# WCE_NanEyeC_board.net
KiCad netlist of a schematic drawn in Altium Designer
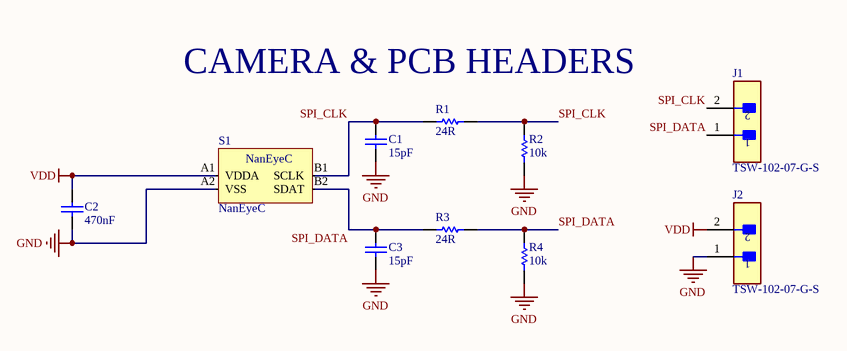
[diagram p0: WCE_NanEyeC_board.SchDoc]

(export (version "E")
  (design (tool "Eeschema 10.0.6"))
  (components
    (comp (ref "C1")
      (value "15pF")
      (footprint "CAPC1608X90X35NL15T15")
      (fields
        (field (name "MANUFACTURER") "AVX Interconnect / Elco")
        (field (name "PART NUMBER") "06035D104KAT2A")
      )
      (libsource (lib "Altium Content Vault") (part "CAP"))
    )
    (comp (ref "C2")
      (value "470nF")
      (footprint "CAPC1608X90X35NL15T15")
      (fields
        (field (name "MANUFACTURER") "AVX Interconnect / Elco")
        (field (name "PART NUMBER") "06035D104KAT2A")
      )
      (libsource (lib "Altium Content Vault") (part "CAP"))
    )
    (comp (ref "C3")
      (value "15pF")
      (footprint "CAPC1608X90X35NL15T15")
      (fields
        (field (name "MANUFACTURER") "AVX Interconnect / Elco")
        (field (name "PART NUMBER") "06035D104KAT2A")
      )
      (libsource (lib "Altium Content Vault") (part "CAP"))
    )
    (comp (ref "J1")
      (value "TSW-102-07-G-S")
      (footprint "FP-TSW-102-07-G-S-MFG")
      (description "CONN HEADER VERT 2POS 2.54MM")
      (fields
        (field (name "MANUFACTURER") "Samtec")
        (field (name "OCTOPART") "https://octopart.com/tsw-102-07-g-s-samtec-272197")
      )
      (libsource (lib "Altium Content Vault") (part "3bc925449376181038e59eaffc5286c"))
    )
    (comp (ref "J2")
      (value "TSW-102-07-G-S")
      (footprint "FP-TSW-102-07-G-S-MFG")
      (description "CONN HEADER VERT 2POS 2.54MM")
      (fields
        (field (name "MANUFACTURER") "Samtec")
        (field (name "OCTOPART") "https://octopart.com/tsw-102-07-g-s-samtec-272197")
      )
      (libsource (lib "Altium Content Vault") (part "3bc925449376181038e59eaffc5286c"))
    )
    (comp (ref "R1")
      (value "24R")
      (footprint "RESC1608X50X30ML20T20")
      (fields (field (name "PART NUMBER") "RR0816P-4640-D-65A") (field (name "MANUFACTURER") "Susumu"))
      (libsource (lib "Altium Content Vault") (part "RES"))
    )
    (comp (ref "R2")
      (value "10k")
      (footprint "RESC1608X50X30ML20T20")
      (fields (field (name "PART NUMBER") "RR0816P-4640-D-65A") (field (name "MANUFACTURER") "Susumu"))
      (libsource (lib "Altium Content Vault") (part "RES"))
    )
    (comp (ref "R3")
      (value "24R")
      (footprint "RESC1608X50X30ML20T20")
      (fields (field (name "PART NUMBER") "RR0816P-4640-D-65A") (field (name "MANUFACTURER") "Susumu"))
      (libsource (lib "Altium Content Vault") (part "RES"))
    )
    (comp (ref "R4")
      (value "10k")
      (footprint "RESC1608X50X30ML20T20")
      (fields (field (name "PART NUMBER") "RR0816P-4640-D-65A") (field (name "MANUFACTURER") "Susumu"))
      (libsource (lib "Altium Content Vault") (part "RES"))
    )
    (comp (ref "S1")
      (value "NanEyeC")
      (footprint "NanEyeC")
      (description "Camera module NanEyeC from AMS. The Part will be delivered by us")
      (libsource (lib "WCE_thesis") (part "NanEyeC"))
    )
  )
  (nets
    (net (code "1") (name "/SPI_CLK") (class "Default")
      (node (ref "C1") (pin "2") (pinfunction "2_2") (pintype "passive"))
      (node (ref "J1") (pin "2") (pinfunction "2_2") (pintype "passive"))
      (node (ref "R1") (pin "1") (pinfunction "1_1") (pintype "passive"))
      (node (ref "R1") (pin "2") (pinfunction "2_2") (pintype "passive"))
      (node (ref "R2") (pin "2") (pinfunction "2_2") (pintype "passive"))
      (node (ref "S1") (pin "B1") (pinfunction "SCLK_B1") (pintype "power_in"))
    )
    (net (code "2") (name "/SPI_DATA") (class "Default")
      (node (ref "C3") (pin "2") (pinfunction "2_2") (pintype "passive"))
      (node (ref "J1") (pin "1") (pinfunction "1_1") (pintype "passive"))
      (node (ref "R3") (pin "1") (pinfunction "1_1") (pintype "passive"))
      (node (ref "R3") (pin "2") (pinfunction "2_2") (pintype "passive"))
      (node (ref "R4") (pin "2") (pinfunction "2_2") (pintype "passive"))
      (node (ref "S1") (pin "B2") (pinfunction "SDAT_B2") (pintype "passive"))
    )
    (net (code "3") (name "GND") (class "Default")
      (node (ref "C1") (pin "1") (pinfunction "1_1") (pintype "passive"))
      (node (ref "C2") (pin "1") (pinfunction "1_1") (pintype "passive"))
      (node (ref "C3") (pin "1") (pinfunction "1_1") (pintype "passive"))
      (node (ref "J2") (pin "1") (pinfunction "1_1") (pintype "passive"))
      (node (ref "R2") (pin "1") (pinfunction "1_1") (pintype "passive"))
      (node (ref "R4") (pin "1") (pinfunction "1_1") (pintype "passive"))
      (node (ref "S1") (pin "A2") (pinfunction "VSS_A2") (pintype "passive"))
    )
    (net (code "4") (name "VDD") (class "Default")
      (node (ref "C2") (pin "2") (pinfunction "2_2") (pintype "passive"))
      (node (ref "J2") (pin "2") (pinfunction "2_2") (pintype "passive"))
      (node (ref "S1") (pin "A1") (pinfunction "VDDA_A1") (pintype "power_in"))
    )
  )
)
